# platform_driver_all2.net
KiCad netlist of a schematic drawn in EAGLE
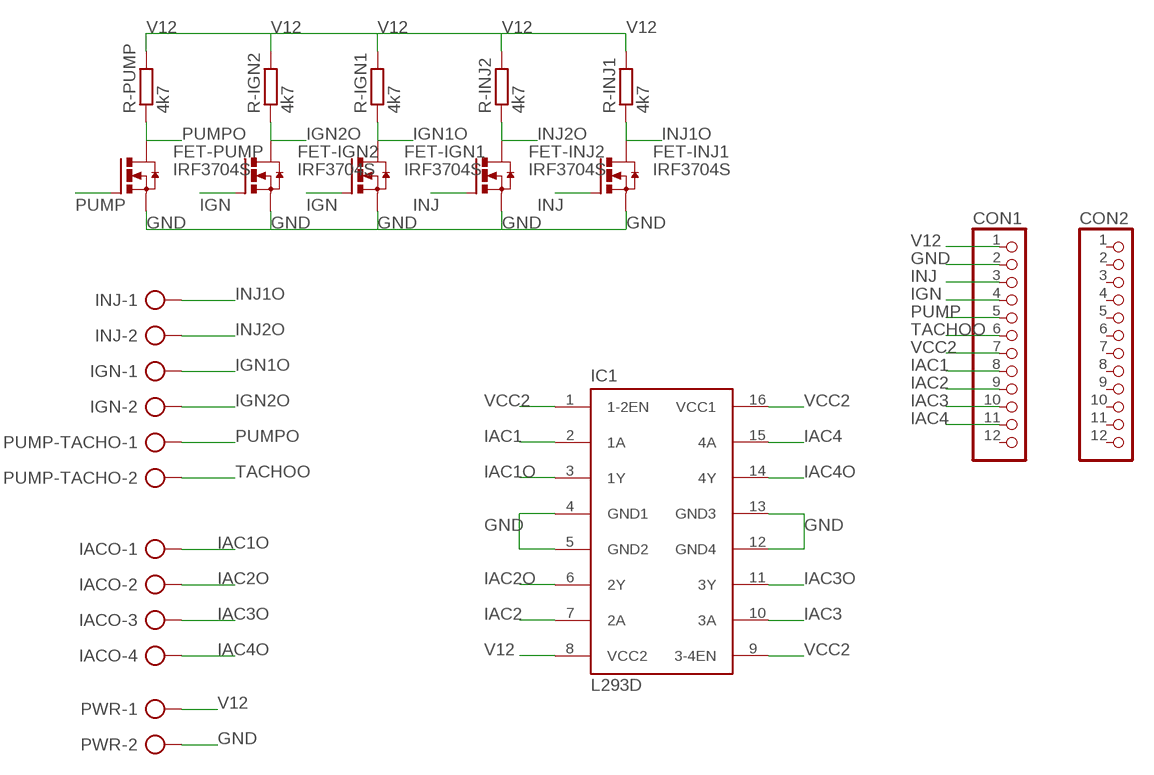
[diagram p0: schematic, sheet 1]

(export (version "E")
  (design (tool "Eeschema 10.0.6"))
  (components
    (comp (ref "CON1")
      (value "PINHD-1X12")
      (footprint "eagle-import:1X12")
      (libsource (lib "eagle-import") (part "PINHD-1X12"))
    )
    (comp (ref "CON2")
      (value "PINHD-1X12")
      (footprint "eagle-import:1X12")
      (libsource (lib "eagle-import") (part "PINHD-1X12"))
    )
    (comp (ref "FET-IGN1")
      (value "IRF3704S")
      (footprint "eagle-import:D2PACK")
      (libsource (lib "eagle-import") (part "IRF3704S"))
    )
    (comp (ref "FET-IGN2")
      (value "IRF3704S")
      (footprint "eagle-import:D2PACK")
      (libsource (lib "eagle-import") (part "IRF3704S"))
    )
    (comp (ref "FET-INJ1")
      (value "IRF3704S")
      (footprint "eagle-import:D2PACK")
      (libsource (lib "eagle-import") (part "IRF3704S"))
    )
    (comp (ref "FET-INJ2")
      (value "IRF3704S")
      (footprint "eagle-import:D2PACK")
      (libsource (lib "eagle-import") (part "IRF3704S"))
    )
    (comp (ref "FET-PUMP")
      (value "IRF3704S")
      (footprint "eagle-import:D2PACK")
      (libsource (lib "eagle-import") (part "IRF3704S"))
    )
    (comp (ref "IACO")
      (value "AK300/4")
      (footprint "eagle-import:AK300_4")
      (libsource (lib "eagle-import") (part "AK300/4"))
    )
    (comp (ref "IC1")
      (value "L293D")
      (footprint "eagle-import:DIL16")
      (libsource (lib "eagle-import") (part "L293D"))
    )
    (comp (ref "IGN")
      (value "AK300/2")
      (footprint "eagle-import:AK300_2")
      (libsource (lib "eagle-import") (part "AK300/2"))
    )
    (comp (ref "INJ")
      (value "AK300/2")
      (footprint "eagle-import:AK300_2")
      (libsource (lib "eagle-import") (part "AK300/2"))
    )
    (comp (ref "PUMP-TACHO")
      (value "AK300/2")
      (footprint "eagle-import:AK300_2")
      (libsource (lib "eagle-import") (part "AK300/2"))
    )
    (comp (ref "PWR")
      (value "AK300/2")
      (footprint "eagle-import:AK300_2")
      (libsource (lib "eagle-import") (part "AK300/2"))
    )
    (comp (ref "R-IGN1")
      (value "4k7")
      (footprint "eagle-import:M1206")
      (libsource (lib "eagle-import") (part "R-EU_M1206"))
    )
    (comp (ref "R-IGN2")
      (value "4k7")
      (footprint "eagle-import:M1206")
      (libsource (lib "eagle-import") (part "R-EU_M1206"))
    )
    (comp (ref "R-INJ1")
      (value "4k7")
      (footprint "eagle-import:M1206")
      (libsource (lib "eagle-import") (part "R-EU_M1206"))
    )
    (comp (ref "R-INJ2")
      (value "4k7")
      (footprint "eagle-import:M1206")
      (libsource (lib "eagle-import") (part "R-EU_M1206"))
    )
    (comp (ref "R-PUMP")
      (value "4k7")
      (footprint "eagle-import:M1206")
      (libsource (lib "eagle-import") (part "R-EU_M1206"))
    )
  )
  (nets
    (net (code "1") (name "/GND") (class "Default")
      (node (ref "CON1") (pin "2") (pinfunction "2_2") (pintype "passive"))
      (node (ref "FET-IGN1") (pin "3") (pinfunction "S_3") (pintype "passive"))
      (node (ref "FET-IGN2") (pin "3") (pinfunction "S_3") (pintype "passive"))
      (node (ref "FET-INJ1") (pin "3") (pinfunction "S_3") (pintype "passive"))
      (node (ref "FET-INJ2") (pin "3") (pinfunction "S_3") (pintype "passive"))
      (node (ref "FET-PUMP") (pin "3") (pinfunction "S_3") (pintype "passive"))
      (node (ref "IC1") (pin "12") (pinfunction "GND4_12") (pintype "power_in"))
      (node (ref "IC1") (pin "13") (pinfunction "GND3_13") (pintype "power_in"))
      (node (ref "IC1") (pin "4") (pinfunction "GND1_4") (pintype "power_in"))
      (node (ref "IC1") (pin "5") (pinfunction "GND2_5") (pintype "power_in"))
      (node (ref "PWR") (pin "2") (pinfunction "KL_2") (pintype "passive"))
    )
    (net (code "2") (name "/IAC1") (class "Default")
      (node (ref "CON1") (pin "8") (pinfunction "8_8") (pintype "passive"))
      (node (ref "IC1") (pin "2") (pinfunction "1A_2") (pintype "input"))
    )
    (net (code "3") (name "/IAC1O") (class "Default")
      (node (ref "IACO") (pin "1") (pinfunction "KL_1") (pintype "passive"))
      (node (ref "IC1") (pin "3") (pinfunction "1Y_3") (pintype "output"))
    )
    (net (code "4") (name "/IAC2") (class "Default")
      (node (ref "CON1") (pin "9") (pinfunction "9_9") (pintype "passive"))
      (node (ref "IC1") (pin "7") (pinfunction "2A_7") (pintype "input"))
    )
    (net (code "5") (name "/IAC2O") (class "Default")
      (node (ref "IACO") (pin "2") (pinfunction "KL_2") (pintype "passive"))
      (node (ref "IC1") (pin "6") (pinfunction "2Y_6") (pintype "output"))
    )
    (net (code "6") (name "/IAC3") (class "Default")
      (node (ref "CON1") (pin "10") (pinfunction "10_10") (pintype "passive"))
      (node (ref "IC1") (pin "10") (pinfunction "3A_10") (pintype "input"))
    )
    (net (code "7") (name "/IAC3O") (class "Default")
      (node (ref "IACO") (pin "3") (pinfunction "KL_3") (pintype "passive"))
      (node (ref "IC1") (pin "11") (pinfunction "3Y_11") (pintype "output"))
    )
    (net (code "8") (name "/IAC4") (class "Default")
      (node (ref "CON1") (pin "11") (pinfunction "11_11") (pintype "passive"))
      (node (ref "IC1") (pin "15") (pinfunction "4A_15") (pintype "input"))
    )
    (net (code "9") (name "/IAC4O") (class "Default")
      (node (ref "IACO") (pin "4") (pinfunction "KL_4") (pintype "passive"))
      (node (ref "IC1") (pin "14") (pinfunction "4Y_14") (pintype "output"))
    )
    (net (code "10") (name "/IGN") (class "Default")
      (node (ref "CON1") (pin "4") (pinfunction "4_4") (pintype "passive"))
      (node (ref "FET-IGN1") (pin "1") (pinfunction "G_1") (pintype "passive"))
      (node (ref "FET-IGN2") (pin "1") (pinfunction "G_1") (pintype "passive"))
    )
    (net (code "11") (name "/IGN1O") (class "Default")
      (node (ref "FET-IGN1") (pin "2") (pinfunction "D_2") (pintype "passive"))
      (node (ref "IGN") (pin "1") (pinfunction "KL_1") (pintype "passive"))
      (node (ref "R-IGN1") (pin "1") (pinfunction "1_1") (pintype "passive"))
    )
    (net (code "12") (name "/IGN2O") (class "Default")
      (node (ref "FET-IGN2") (pin "2") (pinfunction "D_2") (pintype "passive"))
      (node (ref "IGN") (pin "2") (pinfunction "KL_2") (pintype "passive"))
      (node (ref "R-IGN2") (pin "1") (pinfunction "1_1") (pintype "passive"))
    )
    (net (code "13") (name "/INJ") (class "Default")
      (node (ref "CON1") (pin "3") (pinfunction "3_3") (pintype "passive"))
      (node (ref "FET-INJ1") (pin "1") (pinfunction "G_1") (pintype "passive"))
      (node (ref "FET-INJ2") (pin "1") (pinfunction "G_1") (pintype "passive"))
    )
    (net (code "14") (name "/INJ1O") (class "Default")
      (node (ref "FET-INJ1") (pin "2") (pinfunction "D_2") (pintype "passive"))
      (node (ref "INJ") (pin "1") (pinfunction "KL_1") (pintype "passive"))
      (node (ref "R-INJ1") (pin "1") (pinfunction "1_1") (pintype "passive"))
    )
    (net (code "15") (name "/INJ2O") (class "Default")
      (node (ref "FET-INJ2") (pin "2") (pinfunction "D_2") (pintype "passive"))
      (node (ref "INJ") (pin "2") (pinfunction "KL_2") (pintype "passive"))
      (node (ref "R-INJ2") (pin "1") (pinfunction "1_1") (pintype "passive"))
    )
    (net (code "16") (name "/PUMP") (class "Default")
      (node (ref "CON1") (pin "5") (pinfunction "5_5") (pintype "passive"))
      (node (ref "FET-PUMP") (pin "1") (pinfunction "G_1") (pintype "passive"))
    )
    (net (code "17") (name "/PUMPO") (class "Default")
      (node (ref "FET-PUMP") (pin "2") (pinfunction "D_2") (pintype "passive"))
      (node (ref "PUMP-TACHO") (pin "1") (pinfunction "KL_1") (pintype "passive"))
      (node (ref "R-PUMP") (pin "1") (pinfunction "1_1") (pintype "passive"))
    )
    (net (code "18") (name "/TACHOO") (class "Default")
      (node (ref "CON1") (pin "6") (pinfunction "6_6") (pintype "passive"))
      (node (ref "PUMP-TACHO") (pin "2") (pinfunction "KL_2") (pintype "passive"))
    )
    (net (code "19") (name "/V12") (class "Default")
      (node (ref "CON1") (pin "1") (pinfunction "1_1") (pintype "passive"))
      (node (ref "IC1") (pin "8") (pinfunction "VCC2_8") (pintype "power_in"))
      (node (ref "PWR") (pin "1") (pinfunction "KL_1") (pintype "passive"))
      (node (ref "R-IGN1") (pin "2") (pinfunction "2_2") (pintype "passive"))
      (node (ref "R-IGN2") (pin "2") (pinfunction "2_2") (pintype "passive"))
      (node (ref "R-INJ1") (pin "2") (pinfunction "2_2") (pintype "passive"))
      (node (ref "R-INJ2") (pin "2") (pinfunction "2_2") (pintype "passive"))
      (node (ref "R-PUMP") (pin "2") (pinfunction "2_2") (pintype "passive"))
    )
    (net (code "20") (name "/VCC2") (class "Default")
      (node (ref "CON1") (pin "7") (pinfunction "7_7") (pintype "passive"))
      (node (ref "IC1") (pin "1") (pinfunction "1-2EN_1") (pintype "input"))
      (node (ref "IC1") (pin "16") (pinfunction "VCC1_16") (pintype "power_in"))
      (node (ref "IC1") (pin "9") (pinfunction "3-4EN_9") (pintype "input"))
    )
    (net (code "21") (name "unconnected-(CON1-Pad12)") (class "Default")
      (node (ref "CON1") (pin "12") (pinfunction "12_12") (pintype "passive"))
    )
    (net (code "22") (name "unconnected-(CON2-Pad1)") (class "Default")
      (node (ref "CON2") (pin "1") (pinfunction "1_1") (pintype "passive"))
    )
    (net (code "23") (name "unconnected-(CON2-Pad2)") (class "Default")
      (node (ref "CON2") (pin "2") (pinfunction "2_2") (pintype "passive"))
    )
    (net (code "24") (name "unconnected-(CON2-Pad3)") (class "Default")
      (node (ref "CON2") (pin "3") (pinfunction "3_3") (pintype "passive"))
    )
    (net (code "25") (name "unconnected-(CON2-Pad4)") (class "Default")
      (node (ref "CON2") (pin "4") (pinfunction "4_4") (pintype "passive"))
    )
    (net (code "26") (name "unconnected-(CON2-Pad5)") (class "Default")
      (node (ref "CON2") (pin "5") (pinfunction "5_5") (pintype "passive"))
    )
    (net (code "27") (name "unconnected-(CON2-Pad6)") (class "Default")
      (node (ref "CON2") (pin "6") (pinfunction "6_6") (pintype "passive"))
    )
    (net (code "28") (name "unconnected-(CON2-Pad7)") (class "Default")
      (node (ref "CON2") (pin "7") (pinfunction "7_7") (pintype "passive"))
    )
    (net (code "29") (name "unconnected-(CON2-Pad8)") (class "Default")
      (node (ref "CON2") (pin "8") (pinfunction "8_8") (pintype "passive"))
    )
    (net (code "30") (name "unconnected-(CON2-Pad9)") (class "Default")
      (node (ref "CON2") (pin "9") (pinfunction "9_9") (pintype "passive"))
    )
    (net (code "31") (name "unconnected-(CON2-Pad10)") (class "Default")
      (node (ref "CON2") (pin "10") (pinfunction "10_10") (pintype "passive"))
    )
    (net (code "32") (name "unconnected-(CON2-Pad11)") (class "Default")
      (node (ref "CON2") (pin "11") (pinfunction "11_11") (pintype "passive"))
    )
    (net (code "33") (name "unconnected-(CON2-Pad12)") (class "Default")
      (node (ref "CON2") (pin "12") (pinfunction "12_12") (pintype "passive"))
    )
  )
)
